# CPU.net
KiCad netlist of a schematic drawn in Altium Designer
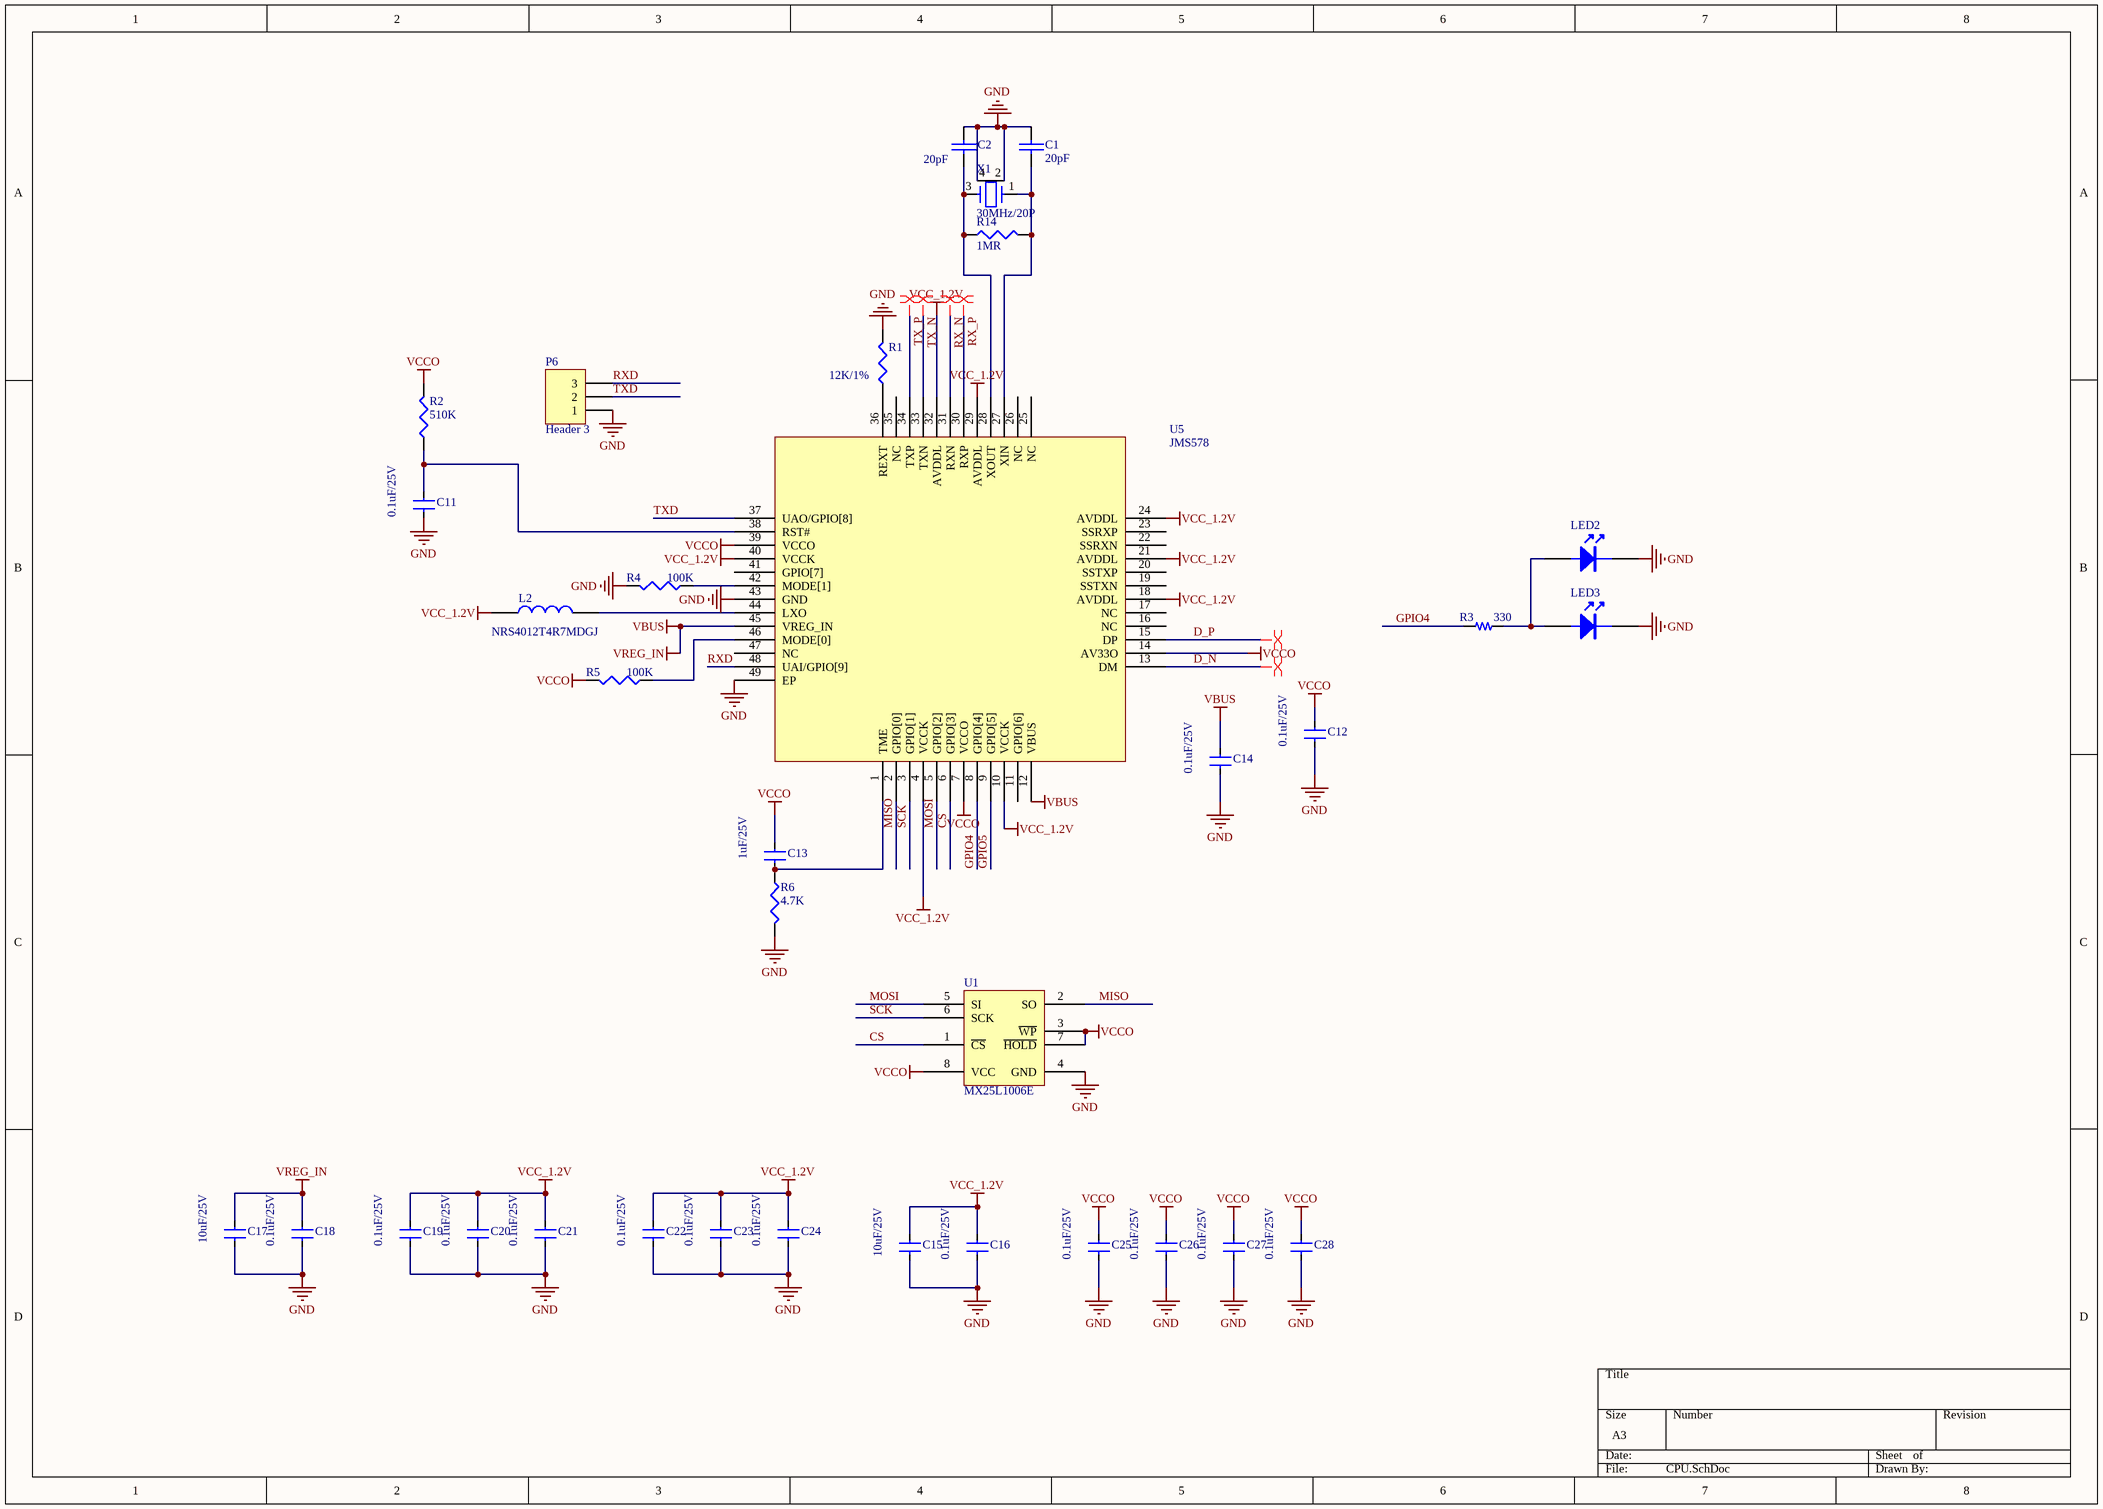
[diagram p0: CPU.SchDoc]

(export (version "E")
  (design (tool "Eeschema 10.0.6"))
  (components
    (comp (ref "C1")
      (value "20pF")
      (footprint "0603c")
      (description "Capacitor")
      (libsource (lib "SM") (part "CAP"))
    )
    (comp (ref "C2")
      (value "20pF")
      (footprint "0603C")
      (description "Capacitor")
      (libsource (lib "SM") (part "CAP"))
    )
    (comp (ref "C11")
      (value "0.1uF/25V")
      (footprint "0603C")
      (description "CCX85-103")
      (libsource (lib "无极性电容") (part "0.01UF"))
    )
    (comp (ref "C12")
      (value "0.1uF/25V")
      (footprint "0603C")
      (description "CCX85-103")
      (libsource (lib "无极性电容") (part "0.01UF"))
    )
    (comp (ref "C13")
      (value "1uF/25V")
      (footprint "0603C")
      (description "CCX85-103")
      (libsource (lib "无极性电容") (part "0.01UF"))
    )
    (comp (ref "C14")
      (value "0.1uF/25V")
      (footprint "0603C")
      (description "CCX85-103")
      (libsource (lib "无极性电容") (part "0.01UF"))
    )
    (comp (ref "C15")
      (value "10uF/25V")
      (footprint "0603C")
      (description "CCX85-103")
      (libsource (lib "无极性电容") (part "0.01UF"))
    )
    (comp (ref "C16")
      (value "0.1uF/25V")
      (footprint "0603C")
      (description "CCX85-103")
      (libsource (lib "无极性电容") (part "0.01UF"))
    )
    (comp (ref "C17")
      (value "10uF/25V")
      (footprint "0603C")
      (description "CCX85-103")
      (libsource (lib "无极性电容") (part "0.01UF"))
    )
    (comp (ref "C18")
      (value "0.1uF/25V")
      (footprint "0603C")
      (description "CCX85-103")
      (libsource (lib "无极性电容") (part "0.01UF"))
    )
    (comp (ref "C19")
      (value "0.1uF/25V")
      (footprint "0603C")
      (description "CCX85-103")
      (libsource (lib "无极性电容") (part "0.01UF"))
    )
    (comp (ref "C20")
      (value "0.1uF/25V")
      (footprint "0603C")
      (description "CCX85-103")
      (libsource (lib "无极性电容") (part "0.01UF"))
    )
    (comp (ref "C21")
      (value "0.1uF/25V")
      (footprint "0603C")
      (description "CCX85-103")
      (libsource (lib "无极性电容") (part "0.01UF"))
    )
    (comp (ref "C22")
      (value "0.1uF/25V")
      (footprint "0603C")
      (description "CCX85-103")
      (libsource (lib "无极性电容") (part "0.01UF"))
    )
    (comp (ref "C23")
      (value "0.1uF/25V")
      (footprint "0603C")
      (description "CCX85-103")
      (libsource (lib "无极性电容") (part "0.01UF"))
    )
    (comp (ref "C24")
      (value "0.1uF/25V")
      (footprint "0603C")
      (description "CCX85-103")
      (libsource (lib "无极性电容") (part "0.01UF"))
    )
    (comp (ref "C25")
      (value "0.1uF/25V")
      (footprint "0603C")
      (description "CCX85-103")
      (libsource (lib "无极性电容") (part "0.01UF"))
    )
    (comp (ref "C26")
      (value "0.1uF/25V")
      (footprint "0603C")
      (description "CCX85-103")
      (libsource (lib "无极性电容") (part "0.01UF"))
    )
    (comp (ref "C27")
      (value "0.1uF/25V")
      (footprint "0603C")
      (description "CCX85-103")
      (libsource (lib "无极性电容") (part "0.01UF"))
    )
    (comp (ref "C28")
      (value "0.1uF/25V")
      (footprint "0603C")
      (description "CCX85-103")
      (libsource (lib "无极性电容") (part "0.01UF"))
    )
    (comp (ref "L2")
      (value "NRS4012T4R7MDGJ")
      (footprint "NRS4012T4R7MDGJ")
      (libsource (lib "*") (part "INDUCTOR"))
    )
    (comp (ref "LED2") (value "~") (footprint "0603LED") (libsource (lib "*") (part "LED")))
    (comp (ref "LED3") (value "~") (footprint "0603LED") (libsource (lib "*") (part "LED")))
    (comp (ref "P6")
      (value "Header 3")
      (footprint "HDR1X3")
      (description "Header, 3-Pin")
      (fields (field (name "PUBLISHER") "Altium Limited"))
      (libsource (lib "Miscellaneous Connectors") (part "Header 3"))
    )
    (comp (ref "R1")
      (value "12K/1%")
      (footprint "0603R")
      (description "Resistor")
      (fields (field (name "PUBLISHER") "Altium Limited"))
      (libsource (lib "SM") (part "Res3"))
    )
    (comp (ref "R2")
      (value "510K")
      (footprint "0603R")
      (description "Resistor")
      (fields (field (name "PUBLISHER") "Altium Limited"))
      (libsource (lib "SM") (part "Res3"))
    )
    (comp (ref "R3") (value "330") (footprint "0603R") (description "R") (libsource (lib "JRJ_1") (part "R")))
    (comp (ref "R4")
      (value "100K")
      (footprint "0603R")
      (description "Resistor")
      (fields (field (name "PUBLISHER") "Altium Limited"))
      (libsource (lib "SM") (part "Res3"))
    )
    (comp (ref "R5")
      (value "100K")
      (footprint "0603R")
      (description "Resistor")
      (fields (field (name "PUBLISHER") "Altium Limited"))
      (libsource (lib "SM") (part "Res3"))
    )
    (comp (ref "R6")
      (value "4.7K")
      (footprint "0603R")
      (description "Resistor")
      (fields (field (name "PUBLISHER") "Altium Limited"))
      (libsource (lib "SM") (part "Res3"))
    )
    (comp (ref "R14")
      (value "1MR")
      (footprint "0603R")
      (description "Resistor")
      (fields (field (name "PUBLISHER") "Altium Limited"))
      (libsource (lib "SM") (part "Res3"))
    )
    (comp (ref "U1")
      (value "MX25L1006E")
      (footprint "SO-8")
      (libsource (lib "Schlib_20110825") (part "M25P40-VMN6"))
    )
    (comp (ref "U5") (value "JMS578") (footprint "QFN400P600-8N") (libsource (lib "stm32") (part "JMS578")))
    (comp (ref "X1")
      (value "30MHz/20P")
      (footprint "XTAL4TN_3225")
      (libsource (lib "JRJ") (part "CRYSTAL_2"))
    )
  )
  (nets
    (net (code "1") (name "/CS") (class "Default")
      (node (ref "U1") (pin "1") (pinfunction "~{CS}_1") (pintype "passive"))
      (node (ref "U5") (pin "6") (pinfunction "GPIO[3]_6") (pintype "passive"))
    )
    (net (code "2") (name "/D_N") (class "Default")
      (node (ref "U5") (pin "13") (pinfunction "DM_13") (pintype "passive"))
    )
    (net (code "3") (name "/D_P") (class "Default")
      (node (ref "U5") (pin "15") (pinfunction "DP_15") (pintype "passive"))
    )
    (net (code "4") (name "/GPIO4") (class "Default")
      (node (ref "R3") (pin "1") (pintype "passive"))
      (node (ref "U5") (pin "8") (pinfunction "GPIO[4]_8") (pintype "passive"))
    )
    (net (code "5") (name "/GPIO5") (class "Default")
      (node (ref "U5") (pin "9") (pinfunction "GPIO[5]_9") (pintype "passive"))
    )
    (net (code "6") (name "/MISO") (class "Default")
      (node (ref "U1") (pin "2") (pinfunction "SO_2") (pintype "passive"))
      (node (ref "U5") (pin "2") (pinfunction "GPIO[0]_2") (pintype "passive"))
    )
    (net (code "7") (name "/MOSI") (class "Default")
      (node (ref "U1") (pin "5") (pinfunction "SI_5") (pintype "passive"))
      (node (ref "U5") (pin "5") (pinfunction "GPIO[2]_5") (pintype "passive"))
    )
    (net (code "8") (name "/RXD") (class "Default")
      (node (ref "P6") (pin "3") (pinfunction "3_3") (pintype "passive"))
      (node (ref "U5") (pin "48") (pinfunction "UAI/GPIO[9]_48") (pintype "passive"))
    )
    (net (code "9") (name "/RX_N") (class "Default")
      (node (ref "U5") (pin "31") (pinfunction "RXN_31") (pintype "passive"))
    )
    (net (code "10") (name "/RX_P") (class "Default")
      (node (ref "U5") (pin "30") (pinfunction "RXP_30") (pintype "passive"))
    )
    (net (code "11") (name "/SCK") (class "Default")
      (node (ref "U1") (pin "6") (pinfunction "SCK_6") (pintype "passive"))
      (node (ref "U5") (pin "3") (pinfunction "GPIO[1]_3") (pintype "passive"))
    )
    (net (code "12") (name "/TXD") (class "Default")
      (node (ref "P6") (pin "2") (pinfunction "2_2") (pintype "passive"))
      (node (ref "U5") (pin "37") (pinfunction "UAO/GPIO[8]_37") (pintype "passive"))
    )
    (net (code "13") (name "/TX_N") (class "Default")
      (node (ref "U5") (pin "33") (pinfunction "TXN_33") (pintype "passive"))
    )
    (net (code "14") (name "/TX_P") (class "Default")
      (node (ref "U5") (pin "34") (pinfunction "TXP_34") (pintype "passive"))
    )
    (net (code "15") (name "GND") (class "Default")
      (node (ref "C1") (pin "1") (pinfunction "1_1") (pintype "passive"))
      (node (ref "C11") (pin "2") (pinfunction "2_2") (pintype "passive"))
      (node (ref "C12") (pin "2") (pinfunction "2_2") (pintype "passive"))
      (node (ref "C14") (pin "2") (pinfunction "2_2") (pintype "passive"))
      (node (ref "C15") (pin "2") (pinfunction "2_2") (pintype "passive"))
      (node (ref "C16") (pin "2") (pinfunction "2_2") (pintype "passive"))
      (node (ref "C17") (pin "2") (pinfunction "2_2") (pintype "passive"))
      (node (ref "C18") (pin "2") (pinfunction "2_2") (pintype "passive"))
      (node (ref "C19") (pin "2") (pinfunction "2_2") (pintype "passive"))
      (node (ref "C2") (pin "1") (pinfunction "1_1") (pintype "passive"))
      (node (ref "C20") (pin "2") (pinfunction "2_2") (pintype "passive"))
      (node (ref "C21") (pin "2") (pinfunction "2_2") (pintype "passive"))
      (node (ref "C22") (pin "2") (pinfunction "2_2") (pintype "passive"))
      (node (ref "C23") (pin "2") (pinfunction "2_2") (pintype "passive"))
      (node (ref "C24") (pin "2") (pinfunction "2_2") (pintype "passive"))
      (node (ref "C25") (pin "2") (pinfunction "2_2") (pintype "passive"))
      (node (ref "C26") (pin "2") (pinfunction "2_2") (pintype "passive"))
      (node (ref "C27") (pin "2") (pinfunction "2_2") (pintype "passive"))
      (node (ref "C28") (pin "2") (pinfunction "2_2") (pintype "passive"))
      (node (ref "LED2") (pin "2") (pinfunction "2_2") (pintype "passive"))
      (node (ref "LED3") (pin "2") (pinfunction "2_2") (pintype "passive"))
      (node (ref "P6") (pin "1") (pinfunction "1_1") (pintype "passive"))
      (node (ref "R1") (pin "2") (pinfunction "2_2") (pintype "passive"))
      (node (ref "R4") (pin "2") (pinfunction "2_2") (pintype "passive"))
      (node (ref "R6") (pin "2") (pinfunction "2_2") (pintype "passive"))
      (node (ref "U1") (pin "4") (pinfunction "GND_4") (pintype "passive"))
      (node (ref "U5") (pin "43") (pinfunction "GND_43") (pintype "passive"))
      (node (ref "U5") (pin "49") (pinfunction "EP_49") (pintype "passive"))
      (node (ref "X1") (pin "2") (pinfunction "GND_2") (pintype "passive"))
      (node (ref "X1") (pin "4") (pinfunction "GND_4") (pintype "passive"))
    )
    (net (code "16") (name "Net-(LED2-Pad1)") (class "Default")
      (node (ref "LED2") (pin "1") (pinfunction "1_1") (pintype "passive"))
      (node (ref "LED3") (pin "1") (pinfunction "1_1") (pintype "passive"))
      (node (ref "R3") (pin "2") (pintype "passive"))
    )
    (net (code "17") (name "Net-(U5-LXO)") (class "Default")
      (node (ref "L2") (pin "2") (pinfunction "2_2") (pintype "passive"))
      (node (ref "U5") (pin "44") (pinfunction "LXO_44") (pintype "passive"))
    )
    (net (code "18") (name "Net-(U5-MODE[0])") (class "Default")
      (node (ref "R5") (pin "1") (pinfunction "1_1") (pintype "passive"))
      (node (ref "U5") (pin "46") (pinfunction "MODE[0]_46") (pintype "passive"))
    )
    (net (code "19") (name "Net-(U5-MODE[1])") (class "Default")
      (node (ref "R4") (pin "1") (pinfunction "1_1") (pintype "passive"))
      (node (ref "U5") (pin "42") (pinfunction "MODE[1]_42") (pintype "passive"))
    )
    (net (code "20") (name "Net-(U5-REXT)") (class "Default")
      (node (ref "R1") (pin "1") (pinfunction "1_1") (pintype "passive"))
      (node (ref "U5") (pin "36") (pinfunction "REXT_36") (pintype "passive"))
    )
    (net (code "21") (name "Net-(U5-RST#)") (class "Default")
      (node (ref "C11") (pin "1") (pinfunction "1_1") (pintype "passive"))
      (node (ref "R2") (pin "1") (pinfunction "1_1") (pintype "passive"))
      (node (ref "U5") (pin "38") (pinfunction "RST#_38") (pintype "passive"))
    )
    (net (code "22") (name "Net-(U5-TME)") (class "Default")
      (node (ref "C13") (pin "2") (pinfunction "2_2") (pintype "passive"))
      (node (ref "R6") (pin "1") (pinfunction "1_1") (pintype "passive"))
      (node (ref "U5") (pin "1") (pinfunction "TME_1") (pintype "passive"))
    )
    (net (code "23") (name "Net-(U5-XIN)") (class "Default")
      (node (ref "C1") (pin "2") (pinfunction "2_2") (pintype "passive"))
      (node (ref "R14") (pin "2") (pinfunction "2_2") (pintype "passive"))
      (node (ref "U5") (pin "27") (pinfunction "XIN_27") (pintype "passive"))
      (node (ref "X1") (pin "1") (pinfunction "X1_1") (pintype "passive"))
    )
    (net (code "24") (name "Net-(U5-XOUT)") (class "Default")
      (node (ref "C2") (pin "2") (pinfunction "2_2") (pintype "passive"))
      (node (ref "R14") (pin "1") (pinfunction "1_1") (pintype "passive"))
      (node (ref "U5") (pin "28") (pinfunction "XOUT_28") (pintype "passive"))
      (node (ref "X1") (pin "3") (pinfunction "X2_3") (pintype "passive"))
    )
    (net (code "25") (name "VBUS") (class "Default")
      (node (ref "C14") (pin "1") (pinfunction "1_1") (pintype "passive"))
      (node (ref "C17") (pin "1") (pinfunction "1_1") (pintype "passive"))
      (node (ref "C18") (pin "1") (pinfunction "1_1") (pintype "passive"))
      (node (ref "U5") (pin "12") (pinfunction "VBUS_12") (pintype "passive"))
      (node (ref "U5") (pin "45") (pinfunction "VREG_IN_45") (pintype "passive"))
    )
    (net (code "26") (name "VCCO") (class "Default")
      (node (ref "C12") (pin "1") (pinfunction "1_1") (pintype "passive"))
      (node (ref "C13") (pin "1") (pinfunction "1_1") (pintype "passive"))
      (node (ref "C25") (pin "1") (pinfunction "1_1") (pintype "passive"))
      (node (ref "C26") (pin "1") (pinfunction "1_1") (pintype "passive"))
      (node (ref "C27") (pin "1") (pinfunction "1_1") (pintype "passive"))
      (node (ref "C28") (pin "1") (pinfunction "1_1") (pintype "passive"))
      (node (ref "R2") (pin "2") (pinfunction "2_2") (pintype "passive"))
      (node (ref "R5") (pin "2") (pinfunction "2_2") (pintype "passive"))
      (node (ref "U1") (pin "3") (pinfunction "~{WP}_3") (pintype "passive"))
      (node (ref "U1") (pin "7") (pinfunction "~{HOLD}_7") (pintype "passive"))
      (node (ref "U1") (pin "8") (pinfunction "VCC_8") (pintype "passive"))
      (node (ref "U5") (pin "14") (pinfunction "AV33O_14") (pintype "passive"))
      (node (ref "U5") (pin "39") (pinfunction "VCCO_39") (pintype "passive"))
      (node (ref "U5") (pin "7") (pinfunction "VCCO_7") (pintype "passive"))
    )
    (net (code "27") (name "VCC_1.2V") (class "Default")
      (node (ref "C15") (pin "1") (pinfunction "1_1") (pintype "passive"))
      (node (ref "C16") (pin "1") (pinfunction "1_1") (pintype "passive"))
      (node (ref "C19") (pin "1") (pinfunction "1_1") (pintype "passive"))
      (node (ref "C20") (pin "1") (pinfunction "1_1") (pintype "passive"))
      (node (ref "C21") (pin "1") (pinfunction "1_1") (pintype "passive"))
      (node (ref "C22") (pin "1") (pinfunction "1_1") (pintype "passive"))
      (node (ref "C23") (pin "1") (pinfunction "1_1") (pintype "passive"))
      (node (ref "C24") (pin "1") (pinfunction "1_1") (pintype "passive"))
      (node (ref "L2") (pin "1") (pinfunction "1_1") (pintype "passive"))
      (node (ref "U5") (pin "10") (pinfunction "VCCK_10") (pintype "passive"))
      (node (ref "U5") (pin "18") (pinfunction "AVDDL_18") (pintype "passive"))
      (node (ref "U5") (pin "21") (pinfunction "AVDDL_21") (pintype "passive"))
      (node (ref "U5") (pin "24") (pinfunction "AVDDL_24") (pintype "passive"))
      (node (ref "U5") (pin "29") (pinfunction "AVDDL_29") (pintype "passive"))
      (node (ref "U5") (pin "32") (pinfunction "AVDDL_32") (pintype "passive"))
      (node (ref "U5") (pin "4") (pinfunction "VCCK_4") (pintype "passive"))
      (node (ref "U5") (pin "40") (pinfunction "VCCK_40") (pintype "passive"))
    )
    (net (code "28") (name "unconnected-(U5-GPIO[6]-Pad11)") (class "Default")
      (node (ref "U5") (pin "11") (pinfunction "GPIO[6]_11") (pintype "passive"))
    )
    (net (code "29") (name "unconnected-(U5-GPIO[7]-Pad41)") (class "Default")
      (node (ref "U5") (pin "41") (pinfunction "GPIO[7]_41") (pintype "passive"))
    )
    (net (code "30") (name "unconnected-(U5-NC-Pad16)") (class "Default")
      (node (ref "U5") (pin "16") (pinfunction "NC_16") (pintype "passive"))
    )
    (net (code "31") (name "unconnected-(U5-NC-Pad17)") (class "Default")
      (node (ref "U5") (pin "17") (pinfunction "NC_17") (pintype "passive"))
    )
    (net (code "32") (name "unconnected-(U5-NC-Pad25)") (class "Default")
      (node (ref "U5") (pin "25") (pinfunction "NC_25") (pintype "passive"))
    )
    (net (code "33") (name "unconnected-(U5-NC-Pad26)") (class "Default")
      (node (ref "U5") (pin "26") (pinfunction "NC_26") (pintype "passive"))
    )
    (net (code "34") (name "unconnected-(U5-NC-Pad35)") (class "Default")
      (node (ref "U5") (pin "35") (pinfunction "NC_35") (pintype "passive"))
    )
    (net (code "35") (name "unconnected-(U5-NC-Pad47)") (class "Default")
      (node (ref "U5") (pin "47") (pinfunction "NC_47") (pintype "passive"))
    )
    (net (code "36") (name "unconnected-(U5-SSRXN-Pad22)") (class "Default")
      (node (ref "U5") (pin "22") (pinfunction "SSRXN_22") (pintype "passive"))
    )
    (net (code "37") (name "unconnected-(U5-SSRXP-Pad23)") (class "Default")
      (node (ref "U5") (pin "23") (pinfunction "SSRXP_23") (pintype "passive"))
    )
    (net (code "38") (name "unconnected-(U5-SSTXN-Pad19)") (class "Default")
      (node (ref "U5") (pin "19") (pinfunction "SSTXN_19") (pintype "passive"))
    )
    (net (code "39") (name "unconnected-(U5-SSTXP-Pad20)") (class "Default")
      (node (ref "U5") (pin "20") (pinfunction "SSTXP_20") (pintype "passive"))
    )
  )
)
